# PowerPCB.net
KiCad netlist of a schematic drawn in EAGLE
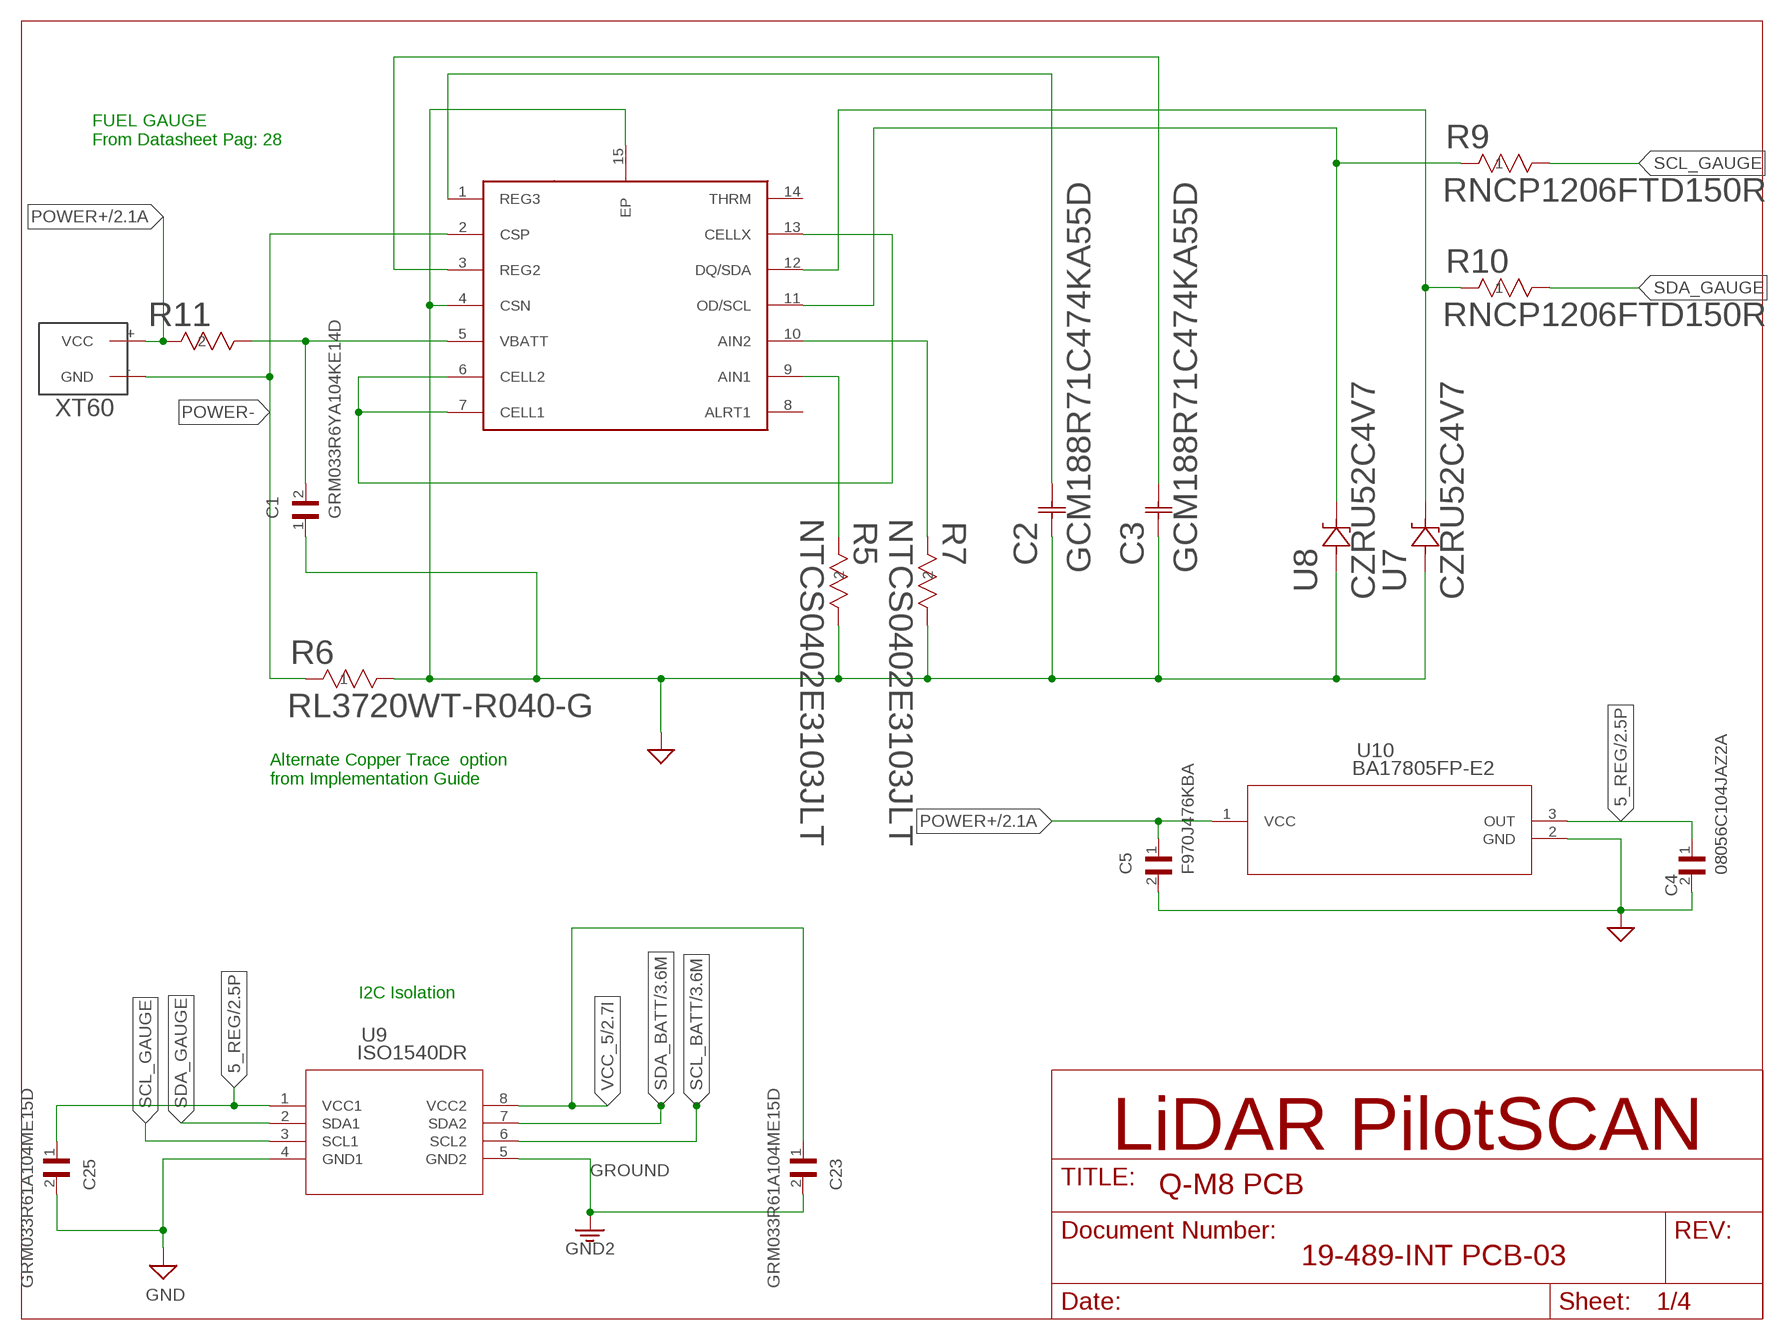
[diagram p0: schematic, sheet 1]
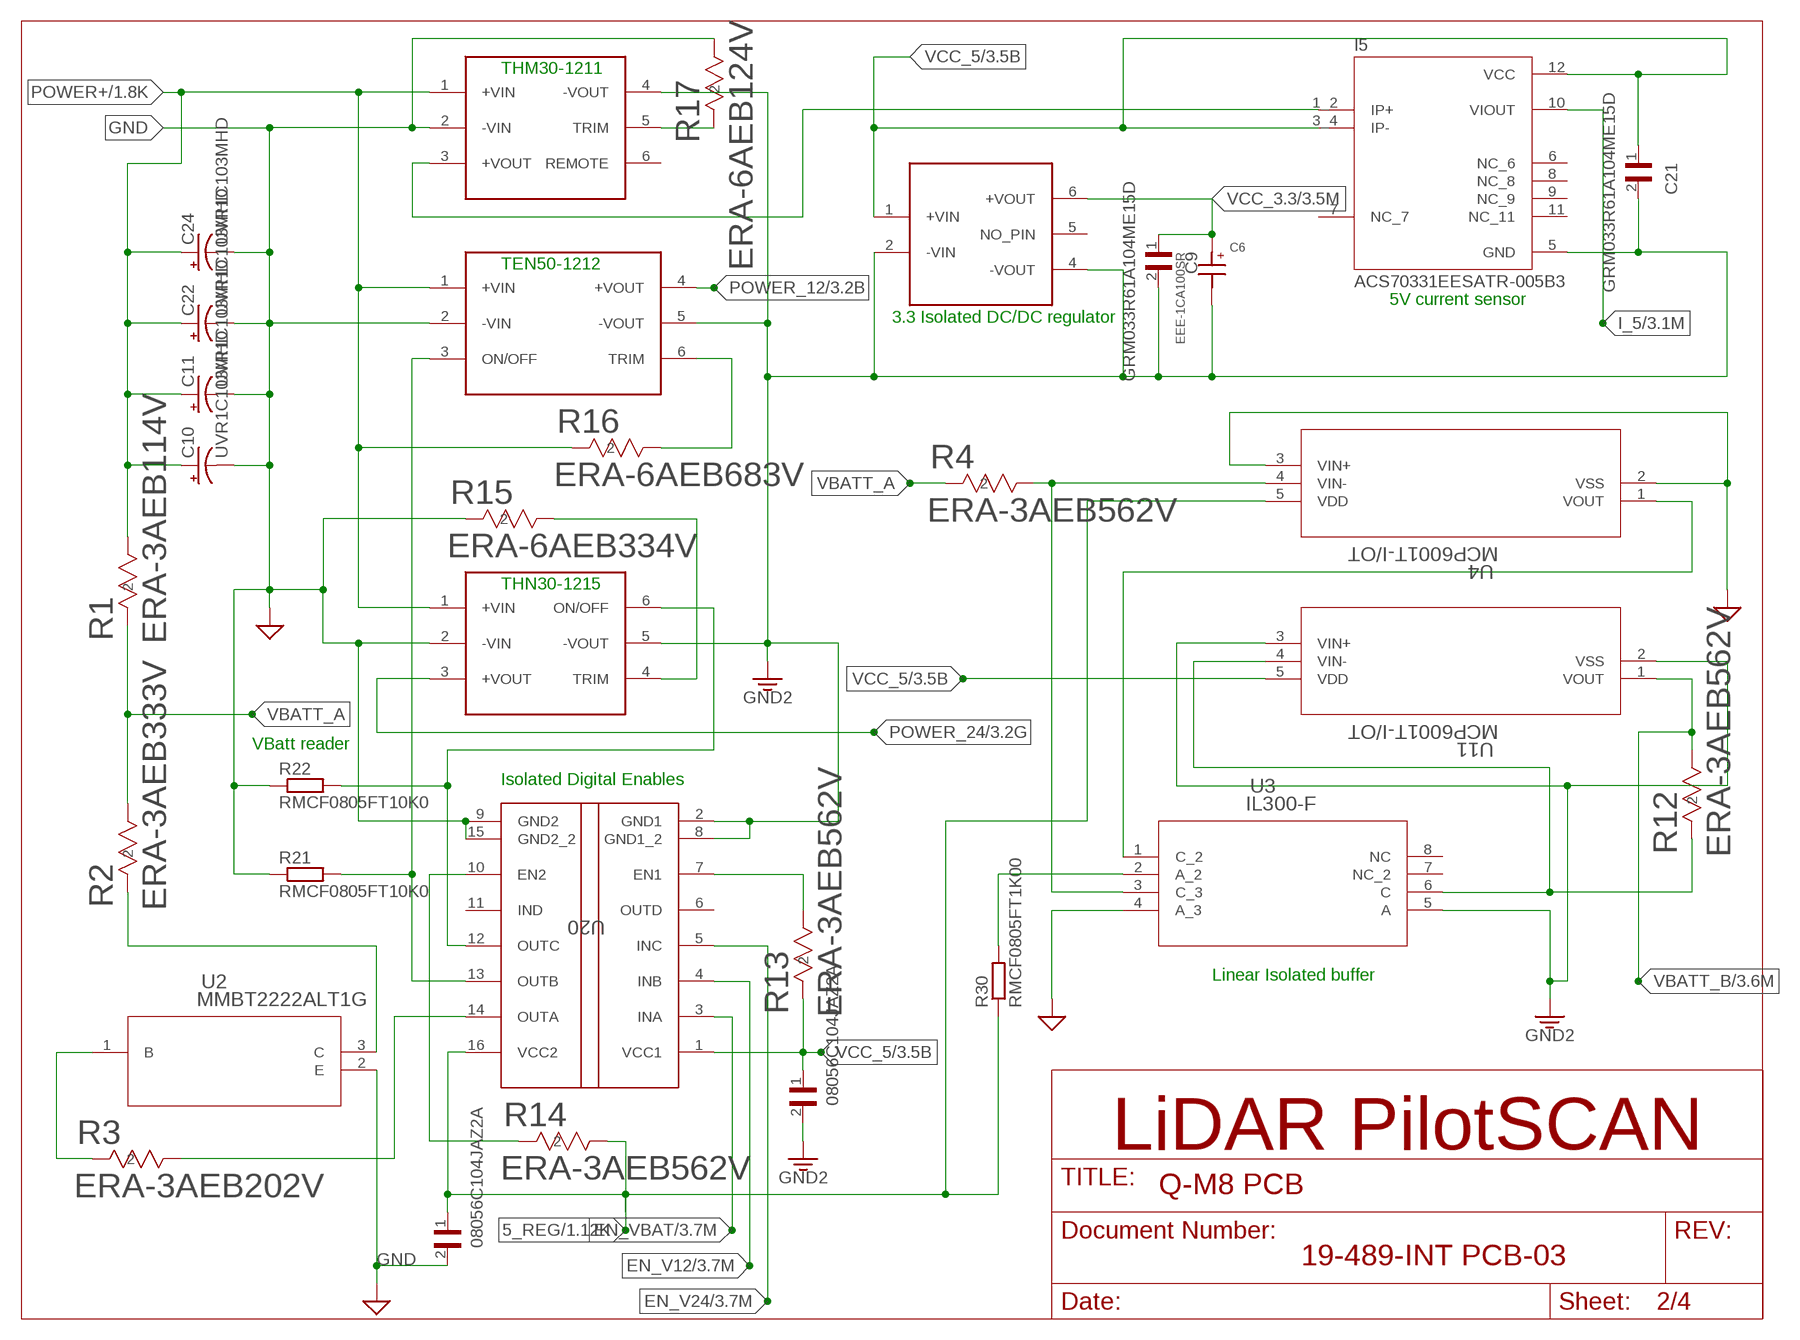
[diagram p1: schematic, sheet 2]
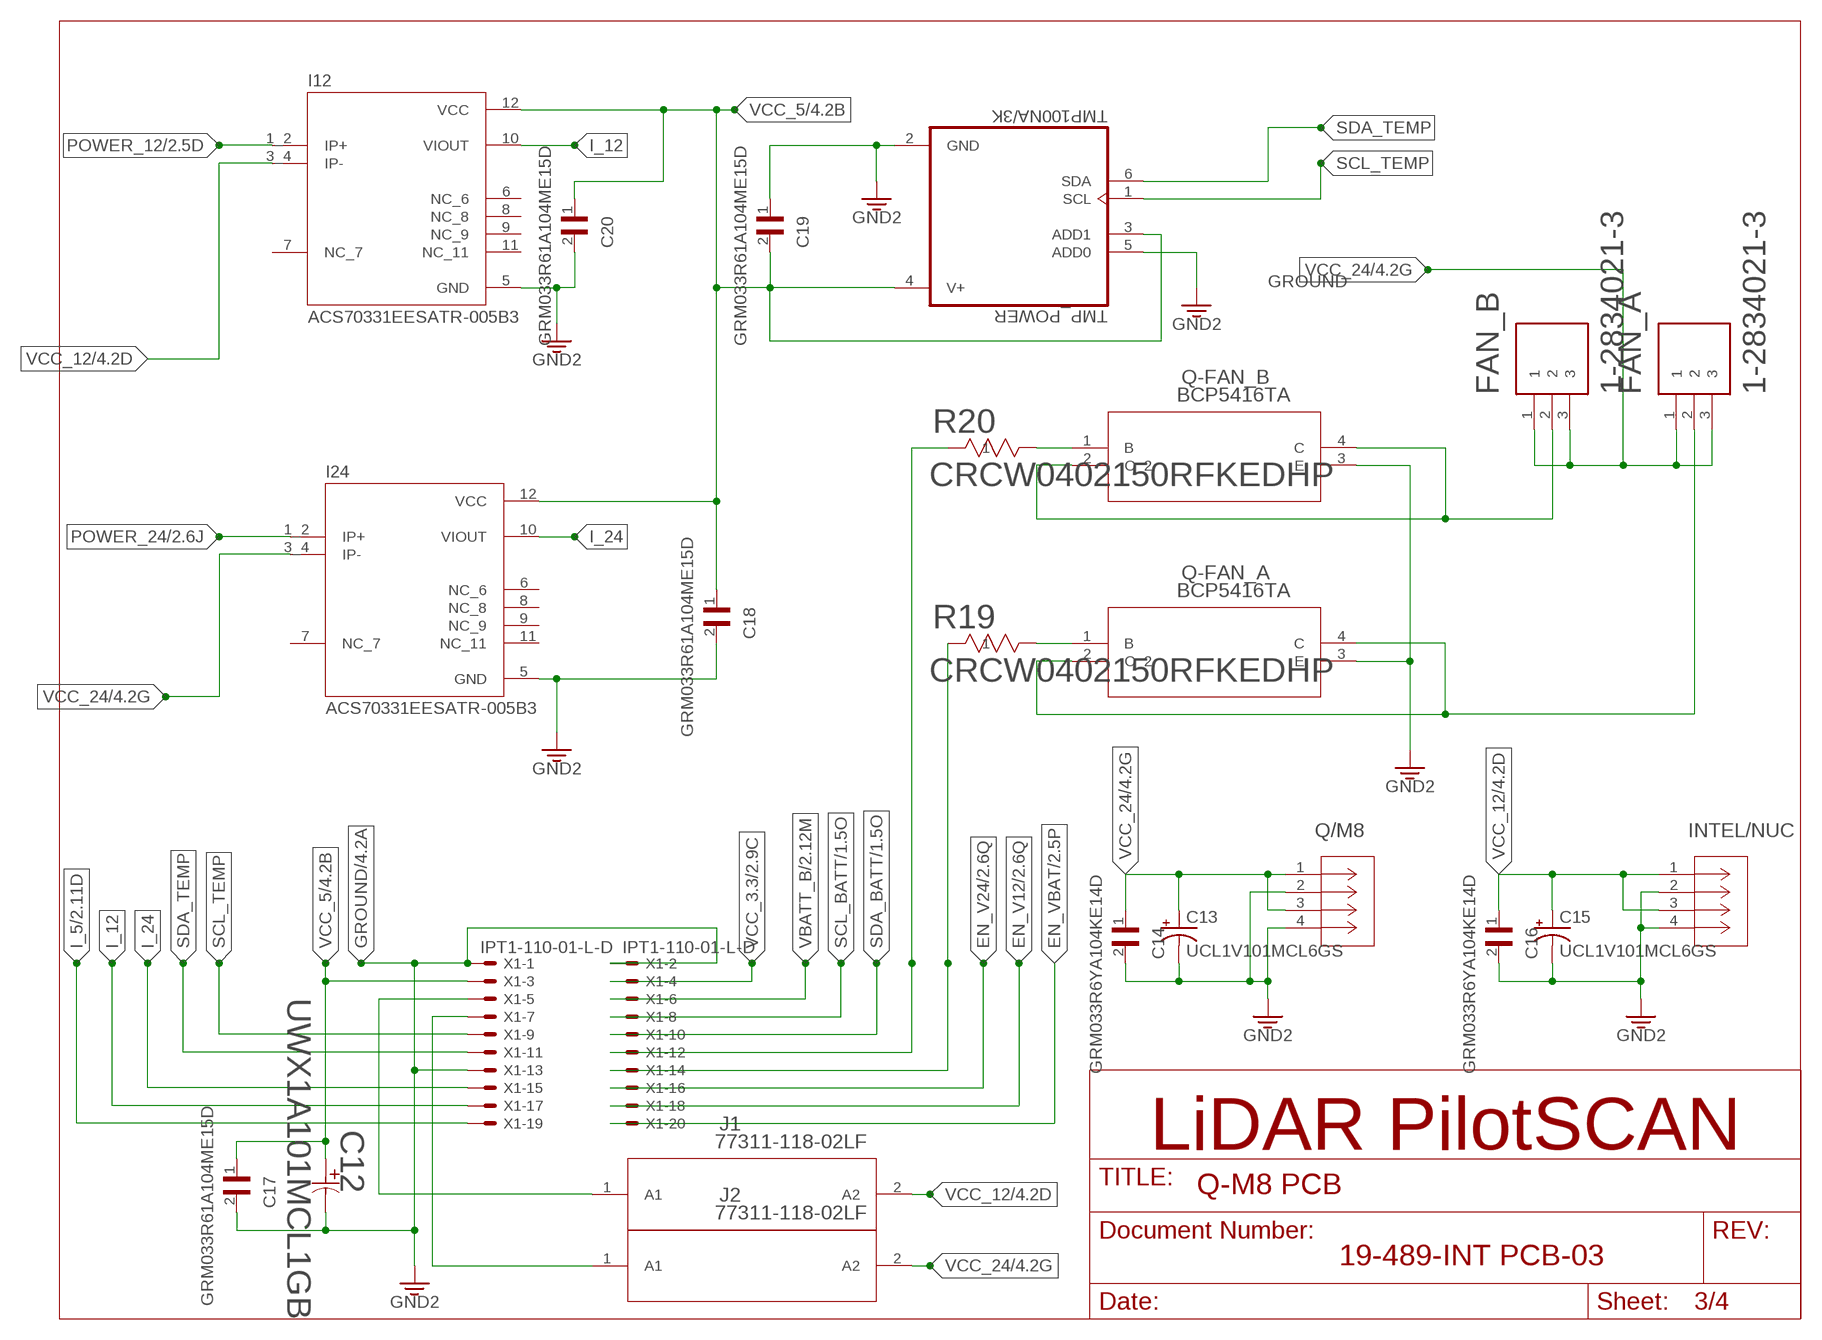
[diagram p2: schematic, sheet 3]
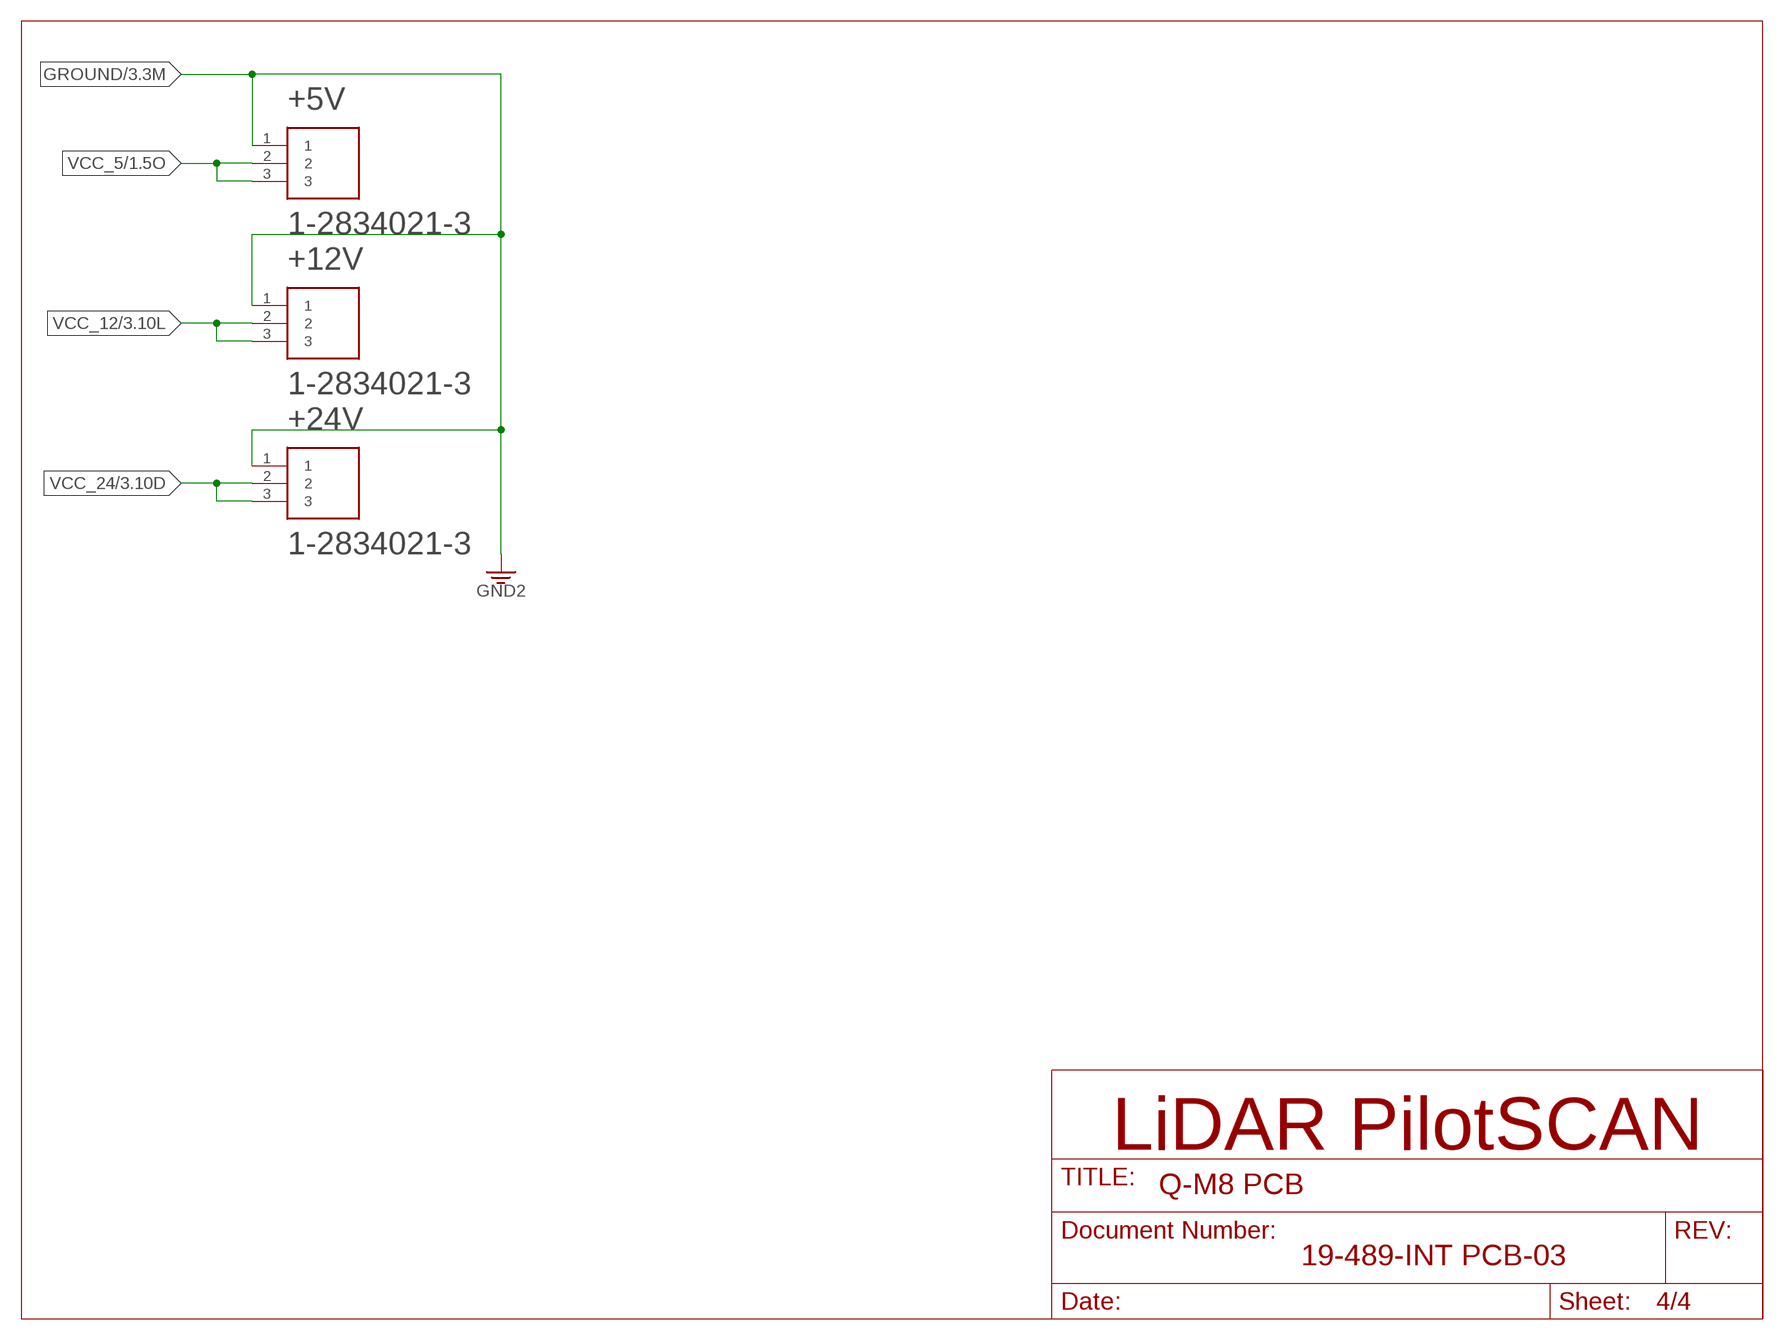
[diagram p3: schematic, sheet 4]

(export (version "E")
  (design (tool "Eeschema 10.0.6"))
  (components
    (comp (ref "+5V")
      (value "1-2834021-3")
      (footprint "eagle-import:CONN_1-2834021-3")
      (fields (field (name "DIGI-KEY_PART_NUMBER") "A123845-ND") (field (name "MF") "TE Connectivity"))
      (libsource (lib "eagle-import") (part "1-2834021-3"))
    )
    (comp (ref "+12V")
      (value "1-2834021-3")
      (footprint "eagle-import:CONN_1-2834021-3")
      (fields (field (name "DIGI-KEY_PART_NUMBER") "A123845-ND") (field (name "MF") "TE Connectivity"))
      (libsource (lib "eagle-import") (part "1-2834021-3"))
    )
    (comp (ref "+24V")
      (value "1-2834021-3")
      (footprint "eagle-import:CONN_1-2834021-3")
      (fields (field (name "DIGI-KEY_PART_NUMBER") "A123845-ND") (field (name "MF") "TE Connectivity"))
      (libsource (lib "eagle-import") (part "1-2834021-3"))
    )
    (comp (ref "C12")
      (value "UWX1A101MCL1GB")
      (footprint "eagle-import:PCAP_6.3X5.4-ELECT")
      (libsource (lib "eagle-import") (part "UWX1A101MCL1GB"))
    )
    (comp (ref "C13")
      (value "UCL1V101MCL6GS")
      (footprint "eagle-import:U2-K")
      (libsource (lib "eagle-import") (part "UCL1V101MCL6GS"))
    )
    (comp (ref "C14")
      (value "GRM033R6YA104KE14D")
      (footprint "eagle-import:CAPC0603X33N")
      (fields (field (name "DIGI-KEY_PART_NUMBER") "490-10430-1-ND") (field (name "MF") "Murata Electronics"))
      (libsource (lib "eagle-import") (part "GRM033R6YA104KE14D"))
    )
    (comp (ref "C15")
      (value "UCL1V101MCL6GS")
      (footprint "eagle-import:U2-K")
      (libsource (lib "eagle-import") (part "UCL1V101MCL6GS"))
    )
    (comp (ref "C16")
      (value "GRM033R6YA104KE14D")
      (footprint "eagle-import:CAPC0603X33N")
      (fields (field (name "DIGI-KEY_PART_NUMBER") "490-10430-1-ND") (field (name "MF") "Murata Electronics"))
      (libsource (lib "eagle-import") (part "GRM033R6YA104KE14D"))
    )
    (comp (ref "C17")
      (value "GRM033R61A104ME15D")
      (footprint "eagle-import:CAPC0603X33N")
      (fields (field (name "DIGI-KEY_PART_NUMBER") "490-5405-1-ND") (field (name "MF") "Murata Electronics"))
      (libsource (lib "eagle-import") (part "GRM033R61A104ME15D"))
    )
    (comp (ref "C18")
      (value "GRM033R61A104ME15D")
      (footprint "eagle-import:CAPC0603X33N")
      (fields (field (name "DIGI-KEY_PART_NUMBER") "490-5405-1-ND") (field (name "MF") "Murata Electronics"))
      (libsource (lib "eagle-import") (part "GRM033R61A104ME15D"))
    )
    (comp (ref "C19")
      (value "GRM033R61A104ME15D")
      (footprint "eagle-import:CAPC0603X33N")
      (fields (field (name "DIGI-KEY_PART_NUMBER") "490-5405-1-ND") (field (name "MF") "Murata Electronics"))
      (libsource (lib "eagle-import") (part "GRM033R61A104ME15D"))
    )
    (comp (ref "C20")
      (value "GRM033R61A104ME15D")
      (footprint "eagle-import:CAPC0603X33N")
      (fields (field (name "DIGI-KEY_PART_NUMBER") "490-5405-1-ND") (field (name "MF") "Murata Electronics"))
      (libsource (lib "eagle-import") (part "GRM033R61A104ME15D"))
    )
    (comp (ref "FAN_A")
      (value "1-2834021-3")
      (footprint "eagle-import:CONN_1-2834021-3")
      (fields (field (name "DIGI-KEY_PART_NUMBER") "A123845-ND") (field (name "MF") "TE Connectivity"))
      (libsource (lib "eagle-import") (part "1-2834021-3"))
    )
    (comp (ref "FAN_B")
      (value "1-2834021-3")
      (footprint "eagle-import:CONN_1-2834021-3")
      (fields (field (name "DIGI-KEY_PART_NUMBER") "A123845-ND") (field (name "MF") "TE Connectivity"))
      (libsource (lib "eagle-import") (part "1-2834021-3"))
    )
    (comp (ref "I12")
      (value "ACS70331EESATR-005B3")
      (footprint "eagle-import:ACS70331EESATR-2P5U3")
      (fields (field (name "MF") "Allegro MicroSystems LLC"))
      (libsource (lib "eagle-import") (part "ACS70331EESATR-005B3"))
    )
    (comp (ref "I24")
      (value "ACS70331EESATR-005B3")
      (footprint "eagle-import:ACS70331EESATR-2P5U3")
      (fields (field (name "MF") "Allegro MicroSystems LLC"))
      (libsource (lib "eagle-import") (part "ACS70331EESATR-005B3"))
    )
    (comp (ref "INTEL/NUC")
      (value "3-794630-4")
      (footprint "eagle-import:CON4_2X2_P3MM_VMNL2")
      (fields (field (name "MANUFACTURER_PART_NUMBER") "37946304"))
      (libsource (lib "eagle-import") (part "3-794630-4"))
    )
    (comp (ref "J1")
      (value "77311-118-02LF")
      (footprint "eagle-import:77311-118-02LF")
      (fields (field (name "MANUFACTURER_PART_NUMBER") "7731111802LF"))
      (libsource (lib "eagle-import") (part "77311-118-02LF"))
    )
    (comp (ref "J2")
      (value "77311-118-02LF")
      (footprint "eagle-import:77311-118-02LF")
      (fields (field (name "MANUFACTURER_PART_NUMBER") "7731111802LF"))
      (libsource (lib "eagle-import") (part "77311-118-02LF"))
    )
    (comp (ref "Q-FAN_A")
      (value "BCP5416TA")
      (footprint "eagle-import:SOT-223")
      (libsource (lib "eagle-import") (part "BCP5416TA"))
    )
    (comp (ref "Q-FAN_B")
      (value "BCP5416TA")
      (footprint "eagle-import:SOT-223")
      (libsource (lib "eagle-import") (part "BCP5416TA"))
    )
    (comp (ref "Q/M8")
      (value "3-794630-4")
      (footprint "eagle-import:CON4_2X2_P3MM_VMNL2")
      (fields (field (name "MANUFACTURER_PART_NUMBER") "37946304"))
      (libsource (lib "eagle-import") (part "3-794630-4"))
    )
    (comp (ref "R19")
      (value "CRCW0402150RFKEDHP")
      (footprint "eagle-import:RES_CRCW_0402")
      (libsource (lib "eagle-import") (part "CRCW0402150RFKEDHP"))
    )
    (comp (ref "R20")
      (value "CRCW0402150RFKEDHP")
      (footprint "eagle-import:RES_CRCW_0402")
      (libsource (lib "eagle-import") (part "CRCW0402150RFKEDHP"))
    )
    (comp (ref "TMP_POWER")
      (value "TMP100NA/3K")
      (footprint "eagle-import:TMP100NA_3K")
      (fields (field (name "MF") "Texas Instruments"))
      (libsource (lib "eagle-import") (part "TMP100NA/3K"))
    )
    (comp (ref "X1")
      (value "IPT1-110-01-L-D")
      (footprint "eagle-import:IPT1-110-01-L-D")
      (libsource (lib "eagle-import") (part "IPT1-110-01-L-D"))
    )
    (comp (ref "C6")
      (value "EEE-1CA100SR")
      (footprint "eagle-import:CAPAE430X550N")
      (fields (field (name "DIGI-KEY_PART_NUMBER") "PCE3878CT-ND") (field (name "MF") "Panasonic"))
      (libsource (lib "eagle-import") (part "EEE-1CA100SR"))
    )
    (comp (ref "C7")
      (value "08056C104JAZ2A")
      (footprint "eagle-import:CAPC2012X140N")
      (fields (field (name "MF") "AVX"))
      (libsource (lib "eagle-import") (part "08056C104JAZ2A"))
    )
    (comp (ref "C8")
      (value "08056C104JAZ2A")
      (footprint "eagle-import:CAPC2012X140N")
      (fields (field (name "MF") "AVX"))
      (libsource (lib "eagle-import") (part "08056C104JAZ2A"))
    )
    (comp (ref "C9")
      (value "GRM033R61A104ME15D")
      (footprint "eagle-import:CAPC0603X33N")
      (fields (field (name "DIGI-KEY_PART_NUMBER") "490-5405-1-ND") (field (name "MF") "Murata Electronics"))
      (libsource (lib "eagle-import") (part "GRM033R61A104ME15D"))
    )
    (comp (ref "C10")
      (value "UVR1C103MHD")
      (footprint "eagle-import:U1-PP")
      (libsource (lib "eagle-import") (part "UVR1C103MHD"))
    )
    (comp (ref "C11")
      (value "UVR1C103MHD")
      (footprint "eagle-import:U1-PP")
      (libsource (lib "eagle-import") (part "UVR1C103MHD"))
    )
    (comp (ref "C21")
      (value "GRM033R61A104ME15D")
      (footprint "eagle-import:CAPC0603X33N")
      (fields (field (name "DIGI-KEY_PART_NUMBER") "490-5405-1-ND") (field (name "MF") "Murata Electronics"))
      (libsource (lib "eagle-import") (part "GRM033R61A104ME15D"))
    )
    (comp (ref "C22")
      (value "UVR1C103MHD")
      (footprint "eagle-import:U1-PP")
      (libsource (lib "eagle-import") (part "UVR1C103MHD"))
    )
    (comp (ref "C24")
      (value "UVR1C103MHD")
      (footprint "eagle-import:U1-PP")
      (libsource (lib "eagle-import") (part "UVR1C103MHD"))
    )
    (comp (ref "DCDC5")
      (value "THM30-1211")
      (footprint "eagle-import:THM30-1211")
      (libsource (lib "eagle-import") (part "THM30-1211"))
    )
    (comp (ref "DCDC12")
      (value "TEN50-1212")
      (footprint "eagle-import:TEN50-1212")
      (libsource (lib "eagle-import") (part "TEN50-1212"))
    )
    (comp (ref "DCDC24")
      (value "THN30-1215")
      (footprint "eagle-import:THN30-1215")
      (libsource (lib "eagle-import") (part "THN30-1215"))
    )
    (comp (ref "I5")
      (value "ACS70331EESATR-005B3")
      (footprint "eagle-import:ACS70331EESATR-2P5U3")
      (fields (field (name "MF") "Allegro MicroSystems LLC"))
      (libsource (lib "eagle-import") (part "ACS70331EESATR-005B3"))
    )
    (comp (ref "R1")
      (value "ERA-3AEB114V")
      (footprint "eagle-import:RC0603N")
      (fields (field (name "MANUFACTURER_PART_NUMBER") "ERA3AEB114V"))
      (libsource (lib "eagle-import") (part "ERA-3AEB114V"))
    )
    (comp (ref "R2")
      (value "ERA-3AEB333V")
      (footprint "eagle-import:RC0603N")
      (fields (field (name "MANUFACTURER_PART_NUMBER") "ERA3AEB333V"))
      (libsource (lib "eagle-import") (part "ERA-3AEB333V"))
    )
    (comp (ref "R3")
      (value "ERA-3AEB202V")
      (footprint "eagle-import:RC0603N")
      (fields (field (name "MANUFACTURER_PART_NUMBER") "ERA3AEB202V"))
      (libsource (lib "eagle-import") (part "ERA-3AEB202V"))
    )
    (comp (ref "R4")
      (value "ERA-3AEB562V")
      (footprint "eagle-import:RC0603N")
      (fields (field (name "MANUFACTURER_PART_NUMBER") "ERA3AEB562V"))
      (libsource (lib "eagle-import") (part "ERA-3AEB562V"))
    )
    (comp (ref "R12")
      (value "ERA-3AEB562V")
      (footprint "eagle-import:RC0603N")
      (fields (field (name "MANUFACTURER_PART_NUMBER") "ERA3AEB562V"))
      (libsource (lib "eagle-import") (part "ERA-3AEB562V"))
    )
    (comp (ref "R13")
      (value "ERA-3AEB562V")
      (footprint "eagle-import:RC0603N")
      (fields (field (name "MANUFACTURER_PART_NUMBER") "ERA3AEB562V"))
      (libsource (lib "eagle-import") (part "ERA-3AEB562V"))
    )
    (comp (ref "R14")
      (value "ERA-3AEB562V")
      (footprint "eagle-import:RC0603N")
      (fields (field (name "MANUFACTURER_PART_NUMBER") "ERA3AEB562V"))
      (libsource (lib "eagle-import") (part "ERA-3AEB562V"))
    )
    (comp (ref "R15")
      (value "ERA-6AEB334V")
      (footprint "eagle-import:RC0805N")
      (fields (field (name "MANUFACTURER_PART_NUMBER") "ERA6AEB334V"))
      (libsource (lib "eagle-import") (part "ERA-6AEB334V"))
    )
    (comp (ref "R16")
      (value "ERA-6AEB683V")
      (footprint "eagle-import:RC0805N")
      (fields (field (name "MANUFACTURER_PART_NUMBER") "ERA6AEB683V"))
      (libsource (lib "eagle-import") (part "ERA-6AEB683V"))
    )
    (comp (ref "R17")
      (value "ERA-6AEB124V")
      (footprint "eagle-import:RC0805N")
      (fields (field (name "MANUFACTURER_PART_NUMBER") "ERA6AEB124V"))
      (libsource (lib "eagle-import") (part "ERA-6AEB124V"))
    )
    (comp (ref "R21")
      (value "RMCF0805FT10K0")
      (footprint "eagle-import:RMCF0805FT10K0")
      (libsource (lib "eagle-import") (part "RMCF0805FT10K0"))
    )
    (comp (ref "R22")
      (value "RMCF0805FT10K0")
      (footprint "eagle-import:RMCF0805FT10K0")
      (libsource (lib "eagle-import") (part "RMCF0805FT10K0"))
    )
    (comp (ref "R30")
      (value "RMCF0805FT1K00")
      (footprint "eagle-import:RMCF0805FT1K00")
      (libsource (lib "eagle-import") (part "RMCF0805FT1K00"))
    )
    (comp (ref "U2")
      (value "MMBT2222ALT1G")
      (footprint "eagle-import:SOT-23")
      (libsource (lib "eagle-import") (part "MMBT2222ALT1G"))
    )
    (comp (ref "U3")
      (value "IL300-F")
      (footprint "eagle-import:DIP8_IL")
      (fields (field (name "MANUFACTURER_PART_NUMBER") "IL300F"))
      (libsource (lib "eagle-import") (part "IL300-F"))
    )
    (comp (ref "U4")
      (value "MCP6001T-I/OT")
      (footprint "eagle-import:SOT-23-5_MC")
      (fields (field (name "MANUFACTURER_PART_NUMBER") "MCP6001TIOT"))
      (libsource (lib "eagle-import") (part "MCP6001T-I/OT"))
    )
    (comp (ref "U6")
      (value "TMV0503SHI")
      (footprint "eagle-import:TMV0503SHI")
      (libsource (lib "eagle-import") (part "TMV0503SHI"))
    )
    (comp (ref "U11")
      (value "MCP6001T-I/OT")
      (footprint "eagle-import:SOT-23-5_MC")
      (fields (field (name "MANUFACTURER_PART_NUMBER") "MCP6001TIOT"))
      (libsource (lib "eagle-import") (part "MCP6001T-I/OT"))
    )
    (comp (ref "U20")
      (value "ISO7741DBQR")
      (footprint "eagle-import:DBQ0016A_N")
      (libsource (lib "eagle-import") (part "ISO7741DBQR"))
    )
    (comp (ref "C1")
      (value "GRM033R6YA104KE14D")
      (footprint "eagle-import:CAPC0603X33N")
      (fields (field (name "DIGI-KEY_PART_NUMBER") "490-10430-1-ND") (field (name "MF") "Murata Electronics"))
      (libsource (lib "eagle-import") (part "GRM033R6YA104KE14D"))
    )
    (comp (ref "C2")
      (value "GCM188R71C474KA55D")
      (footprint "eagle-import:G-188")
      (libsource (lib "eagle-import") (part "GCM188R71C474KA55D"))
    )
    (comp (ref "C3")
      (value "GCM188R71C474KA55D")
      (footprint "eagle-import:G-188")
      (libsource (lib "eagle-import") (part "GCM188R71C474KA55D"))
    )
    (comp (ref "C4")
      (value "08056C104JAZ2A")
      (footprint "eagle-import:CAPC2012X140N")
      (fields (field (name "MF") "AVX"))
      (libsource (lib "eagle-import") (part "08056C104JAZ2A"))
    )
    (comp (ref "C5")
      (value "F970J476KBA")
      (footprint "eagle-import:CAPPC3528X210N")
      (fields (field (name "MF") "AVX"))
      (libsource (lib "eagle-import") (part "F970J476KBA"))
    )
    (comp (ref "C23")
      (value "GRM033R61A104ME15D")
      (footprint "eagle-import:CAPC0603X33N")
      (fields (field (name "DIGI-KEY_PART_NUMBER") "490-5405-1-ND") (field (name "MF") "Murata Electronics"))
      (libsource (lib "eagle-import") (part "GRM033R61A104ME15D"))
    )
    (comp (ref "C25")
      (value "GRM033R61A104ME15D")
      (footprint "eagle-import:CAPC0603X33N")
      (fields (field (name "DIGI-KEY_PART_NUMBER") "490-5405-1-ND") (field (name "MF") "Murata Electronics"))
      (libsource (lib "eagle-import") (part "GRM033R61A104ME15D"))
    )
    (comp (ref "J5")
      (value "XT60")
      (footprint "eagle-import:XT60")
      (libsource (lib "eagle-import") (part "XT60"))
    )
    (comp (ref "R5")
      (value "NTCS0402E3103JLT")
      (footprint "eagle-import:RES_0402_NTC")
      (libsource (lib "eagle-import") (part "NTCS0402E3103JLT"))
    )
    (comp (ref "R6")
      (value "RL3720WT-R040-G")
      (footprint "eagle-import:RES_2037")
      (fields (field (name "MANUFACTURER_PART_NUMBER") "RL3720WTR040G"))
      (libsource (lib "eagle-import") (part "RL3720WT-R040-G"))
    )
    (comp (ref "R7")
      (value "NTCS0402E3103JLT")
      (footprint "eagle-import:RES_0402_NTC")
      (libsource (lib "eagle-import") (part "NTCS0402E3103JLT"))
    )
    (comp (ref "R9")
      (value "RNCP1206FTD150R")
      (footprint "eagle-import:STA_RNCP1206")
      (libsource (lib "eagle-import") (part "RNCP1206FTD150R"))
    )
    (comp (ref "R10")
      (value "RNCP1206FTD150R")
      (footprint "eagle-import:STA_RNCP1206")
      (libsource (lib "eagle-import") (part "RNCP1206FTD150R"))
    )
    (comp (ref "R11")
      (value "ERA-2AKD100X")
      (footprint "eagle-import:RC0402N")
      (fields (field (name "MANUFACTURER_PART_NUMBER") "ERA2AKD100X"))
      (libsource (lib "eagle-import") (part "ERA-2AKD100X"))
    )
    (comp (ref "U5")
      (value "MAX17205G+T")
      (footprint "eagle-import:MAX17205G+T")
      (fields (field (name "MANUFACTURER") "Maxim Integrated"))
      (libsource (lib "eagle-import") (part "MAX17205G+T"))
    )
    (comp (ref "U7")
      (value "CZRU52C4V7")
      (footprint "eagle-import:CZRU")
      (libsource (lib "eagle-import") (part "CZRU52C4V7"))
    )
    (comp (ref "U8")
      (value "CZRU52C4V7")
      (footprint "eagle-import:CZRU")
      (libsource (lib "eagle-import") (part "CZRU52C4V7"))
    )
    (comp (ref "U9")
      (value "ISO1540DR")
      (footprint "eagle-import:D8")
      (libsource (lib "eagle-import") (part "ISO1540DR"))
    )
    (comp (ref "U10")
      (value "BA17805FP-E2")
      (footprint "eagle-import:TO252-3")
      (fields (field (name "MANUFACTURER_PART_NUMBER") "BA17805FPE2"))
      (libsource (lib "eagle-import") (part "BA17805FP-E2"))
    )
  )
  (nets
    (net (code "1") (name "5_REG") (class "Default")
      (node (ref "C25") (pin "1") (pinfunction "1_1") (pintype "passive"))
      (node (ref "C4") (pin "1") (pinfunction "1_1") (pintype "passive"))
      (node (ref "C8") (pin "1") (pinfunction "1_1") (pintype "passive"))
      (node (ref "R14") (pin "1") (pinfunction "1_1") (pintype "passive"))
      (node (ref "R30") (pin "1") (pinfunction "1_1") (pintype "passive"))
      (node (ref "U10") (pin "3") (pinfunction "OUT_3") (pintype "output"))
      (node (ref "U20") (pin "16") (pinfunction "VCC2_16") (pintype "power_in"))
      (node (ref "U4") (pin "5") (pinfunction "VDD_5") (pintype "passive"))
      (node (ref "U9") (pin "1") (pinfunction "VCC1_1") (pintype "power_in"))
    )
    (net (code "2") (name "EN_V12") (class "Default")
      (node (ref "U20") (pin "4") (pinfunction "INB_4") (pintype "input"))
      (node (ref "X1") (pin "P$18") (pinfunction "S_P$18") (pintype "passive"))
    )
    (net (code "3") (name "EN_V24") (class "Default")
      (node (ref "U20") (pin "5") (pinfunction "INC_5") (pintype "input"))
      (node (ref "X1") (pin "P$16") (pinfunction "S_P$16") (pintype "passive"))
    )
    (net (code "4") (name "EN_VBAT") (class "Default")
      (node (ref "U20") (pin "3") (pinfunction "INA_3") (pintype "input"))
      (node (ref "X1") (pin "P$20") (pinfunction "S_P$20") (pintype "passive"))
    )
    (net (code "5") (name "GND") (class "Default")
      (node (ref "C1") (pin "1") (pinfunction "1_1") (pintype "passive"))
      (node (ref "C10") (pin "2") (pinfunction "-_2") (pintype "passive"))
      (node (ref "C11") (pin "2") (pinfunction "-_2") (pintype "passive"))
      (node (ref "C2") (pin "1") (pinfunction "1_1") (pintype "passive"))
      (node (ref "C22") (pin "2") (pinfunction "-_2") (pintype "passive"))
      (node (ref "C24") (pin "2") (pinfunction "-_2") (pintype "passive"))
      (node (ref "C25") (pin "2") (pinfunction "2_2") (pintype "passive"))
      (node (ref "C3") (pin "1") (pinfunction "1_1") (pintype "passive"))
      (node (ref "C4") (pin "2") (pinfunction "2_2") (pintype "passive"))
      (node (ref "C5") (pin "2") (pinfunction "2_2") (pintype "passive"))
      (node (ref "C8") (pin "2") (pinfunction "2_2") (pintype "passive"))
      (node (ref "DCDC12") (pin "2") (pinfunction "-VIN_2") (pintype "bidirectional"))
      (node (ref "DCDC24") (pin "2") (pinfunction "-VIN_2") (pintype "bidirectional"))
      (node (ref "DCDC5") (pin "2") (pinfunction "-VIN_2") (pintype "bidirectional"))
      (node (ref "R15") (pin "2") (pinfunction "2_2") (pintype "passive"))
      (node (ref "R17") (pin "1") (pinfunction "1_1") (pintype "passive"))
      (node (ref "R21") (pin "1") (pinfunction "1_1") (pintype "passive"))
      (node (ref "R22") (pin "1") (pinfunction "1_1") (pintype "passive"))
      (node (ref "R5") (pin "1") (pinfunction "1_1") (pintype "passive"))
      (node (ref "R6") (pin "2") (pinfunction "2_2") (pintype "passive"))
      (node (ref "R7") (pin "1") (pinfunction "1_1") (pintype "passive"))
      (node (ref "U10") (pin "2") (pinfunction "GND_2") (pintype "power_in"))
      (node (ref "U2") (pin "2") (pinfunction "E_2") (pintype "passive"))
      (node (ref "U20") (pin "15") (pinfunction "GND2_2_15") (pintype "power_in"))
      (node (ref "U20") (pin "9") (pinfunction "GND2_9") (pintype "power_in"))
      (node (ref "U3") (pin "4") (pinfunction "A_3_4") (pintype "passive"))
      (node (ref "U4") (pin "2") (pinfunction "VSS_2") (pintype "passive"))
      (node (ref "U4") (pin "3") (pinfunction "VIN+_3") (pintype "passive"))
      (node (ref "U5") (pin "15") (pinfunction "EP_15") (pintype "bidirectional"))
      (node (ref "U5") (pin "4") (pinfunction "CSN_4") (pintype "bidirectional"))
      (node (ref "U7") (pin "2") (pinfunction "2_2") (pintype "passive"))
      (node (ref "U8") (pin "2") (pinfunction "2_2") (pintype "passive"))
      (node (ref "U9") (pin "4") (pinfunction "GND1_4") (pintype "power_in"))
    )
    (net (code "6") (name "GROUND") (class "Default")
      (node (ref "+12V") (pin "1") (pinfunction "1_1") (pintype "passive"))
      (node (ref "+24V") (pin "1") (pinfunction "1_1") (pintype "passive"))
      (node (ref "+5V") (pin "1") (pinfunction "1_1") (pintype "passive"))
      (node (ref "C12") (pin "2") (pinfunction "2_2") (pintype "passive"))
      (node (ref "C13") (pin "2") (pinfunction "-_2") (pintype "passive"))
      (node (ref "C14") (pin "2") (pinfunction "2_2") (pintype "passive"))
      (node (ref "C15") (pin "2") (pinfunction "-_2") (pintype "passive"))
      (node (ref "C16") (pin "2") (pinfunction "2_2") (pintype "passive"))
      (node (ref "C17") (pin "2") (pinfunction "2_2") (pintype "passive"))
      (node (ref "C18") (pin "2") (pinfunction "2_2") (pintype "passive"))
      (node (ref "C19") (pin "1") (pinfunction "1_1") (pintype "passive"))
      (node (ref "C20") (pin "2") (pinfunction "2_2") (pintype "passive"))
      (node (ref "C21") (pin "2") (pinfunction "2_2") (pintype "passive"))
      (node (ref "C23") (pin "2") (pinfunction "2_2") (pintype "passive"))
      (node (ref "C6") (pin "2") (pinfunction "2_2") (pintype "passive"))
      (node (ref "C7") (pin "2") (pinfunction "2_2") (pintype "passive"))
      (node (ref "C9") (pin "2") (pinfunction "2_2") (pintype "passive"))
      (node (ref "DCDC12") (pin "5") (pinfunction "-VOUT_5") (pintype "bidirectional"))
      (node (ref "DCDC24") (pin "5") (pinfunction "-VOUT_5") (pintype "bidirectional"))
      (node (ref "DCDC5") (pin "4") (pinfunction "-VOUT_4") (pintype "bidirectional"))
      (node (ref "I12") (pin "5") (pinfunction "GND_5") (pintype "power_in"))
      (node (ref "I24") (pin "5") (pinfunction "GND_5") (pintype "power_in"))
      (node (ref "I5") (pin "5") (pinfunction "GND_5") (pintype "power_in"))
      (node (ref "INTEL/NUC") (pin "2") (pinfunction "2_2") (pintype "passive"))
      (node (ref "INTEL/NUC") (pin "4") (pinfunction "4_4") (pintype "passive"))
      (node (ref "Q-FAN_A") (pin "3") (pinfunction "E_3") (pintype "passive"))
      (node (ref "Q-FAN_B") (pin "3") (pinfunction "E_3") (pintype "passive"))
      (node (ref "Q/M8") (pin "2") (pinfunction "2_2") (pintype "passive"))
      (node (ref "Q/M8") (pin "4") (pinfunction "4_4") (pintype "passive"))
      (node (ref "TMP_POWER") (pin "2") (pinfunction "GND_2") (pintype "power_in"))
      (node (ref "TMP_POWER") (pin "5") (pinfunction "ADD0_5") (pintype "input"))
      (node (ref "U11") (pin "2") (pinfunction "VSS_2") (pintype "passive"))
      (node (ref "U11") (pin "3") (pinfunction "VIN+_3") (pintype "passive"))
      (node (ref "U20") (pin "2") (pinfunction "GND1_2") (pintype "power_in"))
      (node (ref "U20") (pin "8") (pinfunction "GND1_2_8") (pintype "power_in"))
      (node (ref "U3") (pin "5") (pinfunction "A_5") (pintype "passive"))
      (node (ref "U6") (pin "2") (pinfunction "-VIN_2") (pintype "bidirectional"))
      (node (ref "U6") (pin "4") (pinfunction "-VOUT_4") (pintype "bidirectional"))
      (node (ref "U9") (pin "5") (pinfunction "GND2_5") (pintype "power_in"))
      (node (ref "X1") (pin "P$1") (pinfunction "S_P$1") (pintype "passive"))
      (node (ref "X1") (pin "P$13") (pinfunction "S_P$13") (pintype "passive"))
      (node (ref "X1") (pin "P$2") (pinfunction "S_P$2") (pintype "passive"))
    )
    (net (code "7") (name "I_5") (class "Default")
      (node (ref "I5") (pin "10") (pinfunction "VIOUT_10") (pintype "output"))
      (node (ref "X1") (pin "P$19") (pinfunction "S_P$19") (pintype "passive"))
    )
    (net (code "8") (name "I_12") (class "Default")
      (node (ref "I12") (pin "10") (pinfunction "VIOUT_10") (pintype "output"))
      (node (ref "X1") (pin "P$17") (pinfunction "S_P$17") (pintype "passive"))
    )
    (net (code "9") (name "I_24") (class "Default")
      (node (ref "I24") (pin "10") (pinfunction "VIOUT_10") (pintype "output"))
      (node (ref "X1") (pin "P$15") (pinfunction "S_P$15") (pintype "passive"))
    )
    (net (code "10") (name "Net-(DCDC5-+VOUT)") (class "Default")
      (node (ref "DCDC5") (pin "3") (pinfunction "+VOUT_3") (pintype "bidirectional"))
      (node (ref "I5") (pin "1_2") (pinfunction "IP+_1_2") (pintype "input"))
    )
    (net (code "11") (name "Net-(DCDC5-TRIM)") (class "Default")
      (node (ref "DCDC5") (pin "5") (pinfunction "TRIM_5") (pintype "bidirectional"))
      (node (ref "R17") (pin "2") (pinfunction "2_2") (pintype "passive"))
    )
    (net (code "12") (name "Net-(DCDC12-ON{slash}OFF)") (class "Default")
      (node (ref "DCDC12") (pin "3") (pinfunction "ON/OFF_3") (pintype "bidirectional"))
      (node (ref "R21") (pin "2") (pinfunction "2_2") (pintype "passive"))
      (node (ref "U20") (pin "13") (pinfunction "OUTB_13") (pintype "tri_state"))
    )
    (net (code "13") (name "Net-(DCDC12-TRIM)") (class "Default")
      (node (ref "DCDC12") (pin "6") (pinfunction "TRIM_6") (pintype "bidirectional"))
      (node (ref "R16") (pin "1") (pinfunction "1_1") (pintype "passive"))
    )
    (net (code "14") (name "Net-(DCDC24-ON{slash}OFF)") (class "Default")
      (node (ref "DCDC24") (pin "6") (pinfunction "ON/OFF_6") (pintype "bidirectional"))
      (node (ref "R22") (pin "2") (pinfunction "2_2") (pintype "passive"))
      (node (ref "U20") (pin "12") (pinfunction "OUTC_12") (pintype "tri_state"))
    )
    (net (code "15") (name "Net-(DCDC24-TRIM)") (class "Default")
      (node (ref "DCDC24") (pin "4") (pinfunction "TRIM_4") (pintype "bidirectional"))
      (node (ref "R15") (pin "1") (pinfunction "1_1") (pintype "passive"))
    )
    (net (code "16") (name "Net-(J1-A1)") (class "Default")
      (node (ref "J1") (pin "1") (pinfunction "A1_1") (pintype "passive"))
      (node (ref "X1") (pin "P$5") (pinfunction "S_P$5") (pintype "passive"))
    )
    (net (code "17") (name "Net-(J2-A1)") (class "Default")
      (node (ref "J2") (pin "1") (pinfunction "A1_1") (pintype "passive"))
      (node (ref "X1") (pin "P$7") (pinfunction "S_P$7") (pintype "passive"))
    )
    (net (code "18") (name "Net-(Q-FAN_A-B)") (class "Default")
      (node (ref "Q-FAN_A") (pin "1") (pinfunction "B_1") (pintype "passive"))
      (node (ref "R19") (pin "2") (pinfunction "2_2") (pintype "passive"))
    )
    (net (code "19") (name "Net-(Q-FAN_A-C)") (class "Default")
      (node (ref "FAN_A") (pin "2") (pinfunction "2_2") (pintype "passive"))
      (node (ref "Q-FAN_A") (pin "2") (pinfunction "C_2_2") (pintype "passive"))
      (node (ref "Q-FAN_A") (pin "4") (pinfunction "C_4") (pintype "passive"))
    )
    (net (code "20") (name "Net-(Q-FAN_B-B)") (class "Default")
      (node (ref "Q-FAN_B") (pin "1") (pinfunction "B_1") (pintype "passive"))
      (node (ref "R20") (pin "2") (pinfunction "2_2") (pintype "passive"))
    )
    (net (code "21") (name "Net-(Q-FAN_B-C)") (class "Default")
      (node (ref "FAN_B") (pin "2") (pinfunction "2_2") (pintype "passive"))
      (node (ref "Q-FAN_B") (pin "2") (pinfunction "C_2_2") (pintype "passive"))
      (node (ref "Q-FAN_B") (pin "4") (pinfunction "C_4") (pintype "passive"))
    )
    (net (code "22") (name "Net-(U2-B)") (class "Default")
      (node (ref "R3") (pin "2") (pinfunction "2_2") (pintype "passive"))
      (node (ref "U2") (pin "1") (pinfunction "B_1") (pintype "passive"))
    )
    (net (code "23") (name "Net-(U2-C)") (class "Default")
      (node (ref "R2") (pin "2") (pinfunction "2_2") (pintype "passive"))
      (node (ref "U2") (pin "3") (pinfunction "C_3") (pintype "passive"))
    )
    (net (code "24") (name "Net-(U3-A_2)") (class "Default")
      (node (ref "R30") (pin "2") (pinfunction "2_2") (pintype "passive"))
      (node (ref "U3") (pin "2") (pinfunction "A_2_2") (pintype "passive"))
    )
    (net (code "25") (name "Net-(U3-C_2)") (class "Default")
      (node (ref "U3") (pin "1") (pinfunction "C_2_1") (pintype "passive"))
      (node (ref "U4") (pin "1") (pinfunction "VOUT_1") (pintype "passive"))
    )
    (net (code "26") (name "Net-(U3-C_3)") (class "Default")
      (node (ref "R4") (pin "1") (pinfunction "1_1") (pintype "passive"))
      (node (ref "U3") (pin "3") (pinfunction "C_3_3") (pintype "passive"))
      (node (ref "U4") (pin "4") (pinfunction "VIN-_4") (pintype "passive"))
    )
    (net (code "27") (name "Net-(U5-AIN1)") (class "Default")
      (node (ref "R5") (pin "2") (pinfunction "2_2") (pintype "passive"))
      (node (ref "U5") (pin "9") (pinfunction "AIN1_9") (pintype "bidirectional"))
    )
    (net (code "28") (name "Net-(U5-AIN2)") (class "Default")
      (node (ref "R7") (pin "2") (pinfunction "2_2") (pintype "passive"))
      (node (ref "U5") (pin "10") (pinfunction "AIN2_10") (pintype "bidirectional"))
    )
    (net (code "29") (name "Net-(U5-CELL1)") (class "Default")
      (node (ref "U5") (pin "13") (pinfunction "CELLX_13") (pintype "bidirectional"))
      (node (ref "U5") (pin "6") (pinfunction "CELL2_6") (pintype "bidirectional"))
      (node (ref "U5") (pin "7") (pinfunction "CELL1_7") (pintype "bidirectional"))
    )
    (net (code "30") (name "Net-(U5-DQ{slash}SDA)") (class "Default")
      (node (ref "R10") (pin "1") (pinfunction "1_1") (pintype "passive"))
      (node (ref "U5") (pin "12") (pinfunction "DQ/SDA_12") (pintype "bidirectional"))
      (node (ref "U7") (pin "1") (pinfunction "1_1") (pintype "passive"))
    )
    (net (code "31") (name "Net-(U5-OD{slash}SCL)") (class "Default")
      (node (ref "R9") (pin "1") (pinfunction "1_1") (pintype "passive"))
      (node (ref "U5") (pin "11") (pinfunction "OD/SCL_11") (pintype "bidirectional"))
      (node (ref "U8") (pin "1") (pinfunction "1_1") (pintype "passive"))
    )
    (net (code "32") (name "Net-(U5-REG2)") (class "Default")
      (node (ref "C3") (pin "2") (pinfunction "2_2") (pintype "passive"))
      (node (ref "U5") (pin "3") (pinfunction "REG2_3") (pintype "bidirectional"))
    )
    (net (code "33") (name "Net-(U5-REG3)") (class "Default")
      (node (ref "C2") (pin "2") (pinfunction "2_2") (pintype "passive"))
      (node (ref "U5") (pin "1") (pinfunction "REG3_1") (pintype "bidirectional"))
    )
    (net (code "34") (name "Net-(U5-VBATT)") (class "Default")
      (node (ref "C1") (pin "2") (pinfunction "2_2") (pintype "passive"))
      (node (ref "R11") (pin "1") (pinfunction "1_1") (pintype "passive"))
      (node (ref "U5") (pin "5") (pinfunction "VBATT_5") (pintype "bidirectional"))
    )
    (net (code "35") (name "Net-(U11-VIN-)") (class "Default")
      (node (ref "R12") (pin "2") (pinfunction "2_2") (pintype "passive"))
      (node (ref "U11") (pin "4") (pinfunction "VIN-_4") (pintype "passive"))
      (node (ref "U3") (pin "6") (pinfunction "C_6") (pintype "passive"))
    )
    (net (code "36") (name "Net-(U20-EN1)") (class "Default")
      (node (ref "R13") (pin "1") (pinfunction "1_1") (pintype "passive"))
      (node (ref "U20") (pin "7") (pinfunction "EN1_7") (pintype "input"))
    )
    (net (code "37") (name "Net-(U20-EN2)") (class "Default")
      (node (ref "R14") (pin "2") (pinfunction "2_2") (pintype "passive"))
      (node (ref "U20") (pin "10") (pinfunction "EN2_10") (pintype "input"))
    )
    (net (code "38") (name "Net-(U20-OUTA)") (class "Default")
      (node (ref "R3") (pin "1") (pinfunction "1_1") (pintype "passive"))
      (node (ref "U20") (pin "14") (pinfunction "OUTA_14") (pintype "tri_state"))
    )
    (net (code "39") (name "Net-(X1D-S)") (class "Default")
      (node (ref "R20") (pin "1") (pinfunction "1_1") (pintype "passive"))
      (node (ref "X1") (pin "P$12") (pinfunction "S_P$12") (pintype "passive"))
    )
    (net (code "40") (name "Net-(X1F-S)") (class "Default")
      (node (ref "R19") (pin "1") (pinfunction "1_1") (pintype "passive"))
      (node (ref "X1") (pin "P$14") (pinfunction "S_P$14") (pintype "passive"))
    )
    (net (code "41") (name "POWER+") (class "Default")
      (node (ref "C10") (pin "1") (pinfunction "+_1") (pintype "passive"))
      (node (ref "C11") (pin "1") (pinfunction "+_1") (pintype "passive"))
      (node (ref "C22") (pin "1") (pinfunction "+_1") (pintype "passive"))
      (node (ref "C24") (pin "1") (pinfunction "+_1") (pintype "passive"))
      (node (ref "C5") (pin "1") (pinfunction "1_1") (pintype "passive"))
      (node (ref "DCDC12") (pin "1") (pinfunction "+VIN_1") (pintype "bidirectional"))
      (node (ref "DCDC24") (pin "1") (pinfunction "+VIN_1") (pintype "bidirectional"))
      (node (ref "DCDC5") (pin "1") (pinfunction "+VIN_1") (pintype "bidirectional"))
      (node (ref "J5") (pin "+") (pinfunction "VCC_+") (pintype "bidirectional"))
      (node (ref "R1") (pin "1") (pinfunction "1_1") (pintype "passive"))
      (node (ref "R11") (pin "2") (pinfunction "2_2") (pintype "passive"))
      (node (ref "R16") (pin "2") (pinfunction "2_2") (pintype "passive"))
      (node (ref "U10") (pin "1") (pinfunction "VCC_1") (pintype "power_in"))
    )
    (net (code "42") (name "POWER-") (class "Default")
      (node (ref "J5") (pin "-") (pinfunction "GND_-") (pintype "bidirectional"))
      (node (ref "R6") (pin "1") (pinfunction "1_1") (pintype "passive"))
      (node (ref "U5") (pin "2") (pinfunction "CSP_2") (pintype "bidirectional"))
    )
    (net (code "43") (name "POWER_12") (class "Default")
      (node (ref "DCDC12") (pin "4") (pinfunction "+VOUT_4") (pintype "bidirectional"))
      (node (ref "I12") (pin "1_2") (pinfunction "IP+_1_2") (pintype "input"))
    )
    (net (code "44") (name "POWER_24") (class "Default")
      (node (ref "DCDC24") (pin "3") (pinfunction "+VOUT_3") (pintype "bidirectional"))
      (node (ref "I24") (pin "1_2") (pinfunction "IP+_1_2") (pintype "input"))
    )
    (net (code "45") (name "SCL_BATT") (class "Default")
      (node (ref "U9") (pin "6") (pinfunction "SCL2_6") (pintype "bidirectional"))
      (node (ref "X1") (pin "P$8") (pinfunction "S_P$8") (pintype "passive"))
    )
    (net (code "46") (name "SCL_GAUGE") (class "Default")
      (node (ref "R9") (pin "2") (pinfunction "2_2") (pintype "passive"))
      (node (ref "U9") (pin "3") (pinfunction "SCL1_3") (pintype "bidirectional"))
    )
    (net (code "47") (name "SCL_TEMP") (class "Default")
      (node (ref "TMP_POWER") (pin "1") (pinfunction "SCL_1") (pintype "input"))
      (node (ref "X1") (pin "P$9") (pinfunction "S_P$9") (pintype "passive"))
    )
    (net (code "48") (name "SDA_BATT") (class "Default")
      (node (ref "U9") (pin "7") (pinfunction "SDA2_7") (pintype "bidirectional"))
      (node (ref "X1") (pin "P$10") (pinfunction "S_P$10") (pintype "passive"))
    )
    (net (code "49") (name "SDA_GAUGE") (class "Default")
      (node (ref "R10") (pin "2") (pinfunction "2_2") (pintype "passive"))
      (node (ref "U9") (pin "2") (pinfunction "SDA1_2") (pintype "bidirectional"))
    )
    (net (code "50") (name "SDA_TEMP") (class "Default")
      (node (ref "TMP_POWER") (pin "6") (pinfunction "SDA_6") (pintype "bidirectional"))
      (node (ref "X1") (pin "P$11") (pinfunction "S_P$11") (pintype "passive"))
    )
    (net (code "51") (name "VBATT_A") (class "Default")
      (node (ref "R1") (pin "2") (pinfunction "2_2") (pintype "passive"))
      (node (ref "R2") (pin "1") (pinfunction "1_1") (pintype "passive"))
      (node (ref "R4") (pin "2") (pinfunction "2_2") (pintype "passive"))
    )
    (net (code "52") (name "VBATT_B") (class "Default")
      (node (ref "R12") (pin "1") (pinfunction "1_1") (pintype "passive"))
      (node (ref "U11") (pin "1") (pinfunction "VOUT_1") (pintype "passive"))
      (node (ref "X1") (pin "P$6") (pinfunction "S_P$6") (pintype "passive"))
    )
    (net (code "53") (name "VCC_3.3") (class "Default")
      (node (ref "C6") (pin "1") (pinfunction "1_1") (pintype "passive"))
      (node (ref "C9") (pin "1") (pinfunction "1_1") (pintype "passive"))
      (node (ref "U6") (pin "6") (pinfunction "+VOUT_6") (pintype "bidirectional"))
      (node (ref "X1") (pin "P$4") (pinfunction "S_P$4") (pintype "passive"))
    )
    (net (code "54") (name "VCC_5") (class "Default")
      (node (ref "+5V") (pin "2") (pinfunction "2_2") (pintype "passive"))
      (node (ref "+5V") (pin "3") (pinfunction "3_3") (pintype "passive"))
      (node (ref "C12") (pin "1") (pinfunction "1_1") (pintype "passive"))
      (node (ref "C17") (pin "1") (pinfunction "1_1") (pintype "passive"))
      (node (ref "C18") (pin "1") (pinfunction "1_1") (pintype "passive"))
      (node (ref "C19") (pin "2") (pinfunction "2_2") (pintype "passive"))
      (node (ref "C20") (pin "1") (pinfunction "1_1") (pintype "passive"))
      (node (ref "C21") (pin "1") (pinfunction "1_1") (pintype "passive"))
      (node (ref "C23") (pin "1") (pinfunction "1_1") (pintype "passive"))
      (node (ref "C7") (pin "1") (pinfunction "1_1") (pintype "passive"))
      (node (ref "I12") (pin "12") (pinfunction "VCC_12") (pintype "power_in"))
      (node (ref "I24") (pin "12") (pinfunction "VCC_12") (pintype "power_in"))
      (node (ref "I5") (pin "12") (pinfunction "VCC_12") (pintype "power_in"))
      (node (ref "I5") (pin "3_4") (pinfunction "IP-_3_4") (pintype "input"))
      (node (ref "R13") (pin "2") (pinfunction "2_2") (pintype "passive"))
      (node (ref "TMP_POWER") (pin "3") (pinfunction "ADD1_3") (pintype "input"))
      (node (ref "TMP_POWER") (pin "4") (pinfunction "V+_4") (pintype "power_in"))
      (node (ref "U11") (pin "5") (pinfunction "VDD_5") (pintype "passive"))
      (node (ref "U20") (pin "1") (pinfunction "VCC1_1") (pintype "power_in"))
      (node (ref "U6") (pin "1") (pinfunction "+VIN_1") (pintype "bidirectional"))
      (node (ref "U9") (pin "8") (pinfunction "VCC2_8") (pintype "power_in"))
      (node (ref "X1") (pin "P$3") (pinfunction "S_P$3") (pintype "passive"))
    )
    (net (code "55") (name "VCC_12") (class "Default")
      (node (ref "+12V") (pin "2") (pinfunction "2_2") (pintype "passive"))
      (node (ref "+12V") (pin "3") (pinfunction "3_3") (pintype "passive"))
      (node (ref "C15") (pin "1") (pinfunction "+_1") (pintype "passive"))
      (node (ref "C16") (pin "1") (pinfunction "1_1") (pintype "passive"))
      (node (ref "I12") (pin "3_4") (pinfunction "IP-_3_4") (pintype "input"))
      (node (ref "INTEL/NUC") (pin "1") (pinfunction "1_1") (pintype "passive"))
      (node (ref "INTEL/NUC") (pin "3") (pinfunction "3_3") (pintype "passive"))
      (node (ref "J1") (pin "2") (pinfunction "A2_2") (pintype "passive"))
    )
    (net (code "56") (name "VCC_24") (class "Default")
      (node (ref "+24V") (pin "2") (pinfunction "2_2") (pintype "passive"))
      (node (ref "+24V") (pin "3") (pinfunction "3_3") (pintype "passive"))
      (node (ref "C13") (pin "1") (pinfunction "+_1") (pintype "passive"))
      (node (ref "C14") (pin "1") (pinfunction "1_1") (pintype "passive"))
      (node (ref "FAN_A") (pin "1") (pinfunction "1_1") (pintype "passive"))
      (node (ref "FAN_A") (pin "3") (pinfunction "3_3") (pintype "passive"))
      (node (ref "FAN_B") (pin "1") (pinfunction "1_1") (pintype "passive"))
      (node (ref "FAN_B") (pin "3") (pinfunction "3_3") (pintype "passive"))
      (node (ref "I24") (pin "3_4") (pinfunction "IP-_3_4") (pintype "input"))
      (node (ref "J2") (pin "2") (pinfunction "A2_2") (pintype "passive"))
      (node (ref "Q/M8") (pin "1") (pinfunction "1_1") (pintype "passive"))
      (node (ref "Q/M8") (pin "3") (pinfunction "3_3") (pintype "passive"))
    )
    (net (code "57") (name "unconnected-(DCDC5-REMOTE-Pad6)") (class "Default")
      (node (ref "DCDC5") (pin "6") (pinfunction "REMOTE_6") (pintype "bidirectional"))
    )
    (net (code "58") (name "unconnected-(I5-NC_6-Pad6)") (class "Default")
      (node (ref "I5") (pin "6") (pinfunction "NC_6_6") (pintype "passive"))
    )
    (net (code "59") (name "unconnected-(I5-NC_7-Pad7)") (class "Default")
      (node (ref "I5") (pin "7") (pinfunction "NC_7_7") (pintype "passive"))
    )
    (net (code "60") (name "unconnected-(I5-NC_8-Pad8)") (class "Default")
      (node (ref "I5") (pin "8") (pinfunction "NC_8_8") (pintype "passive"))
    )
    (net (code "61") (name "unconnected-(I5-NC_9-Pad9)") (class "Default")
      (node (ref "I5") (pin "9") (pinfunction "NC_9_9") (pintype "passive"))
    )
    (net (code "62") (name "unconnected-(I5-NC_11-Pad11)") (class "Default")
      (node (ref "I5") (pin "11") (pinfunction "NC_11_11") (pintype "passive"))
    )
    (net (code "63") (name "unconnected-(I12-NC_6-Pad6)") (class "Default")
      (node (ref "I12") (pin "6") (pinfunction "NC_6_6") (pintype "passive"))
    )
    (net (code "64") (name "unconnected-(I12-NC_7-Pad7)") (class "Default")
      (node (ref "I12") (pin "7") (pinfunction "NC_7_7") (pintype "passive"))
    )
    (net (code "65") (name "unconnected-(I12-NC_8-Pad8)") (class "Default")
      (node (ref "I12") (pin "8") (pinfunction "NC_8_8") (pintype "passive"))
    )
    (net (code "66") (name "unconnected-(I12-NC_9-Pad9)") (class "Default")
      (node (ref "I12") (pin "9") (pinfunction "NC_9_9") (pintype "passive"))
    )
    (net (code "67") (name "unconnected-(I12-NC_11-Pad11)") (class "Default")
      (node (ref "I12") (pin "11") (pinfunction "NC_11_11") (pintype "passive"))
    )
    (net (code "68") (name "unconnected-(I24-NC_6-Pad6)") (class "Default")
      (node (ref "I24") (pin "6") (pinfunction "NC_6_6") (pintype "passive"))
    )
    (net (code "69") (name "unconnected-(I24-NC_7-Pad7)") (class "Default")
      (node (ref "I24") (pin "7") (pinfunction "NC_7_7") (pintype "passive"))
    )
    (net (code "70") (name "unconnected-(I24-NC_8-Pad8)") (class "Default")
      (node (ref "I24") (pin "8") (pinfunction "NC_8_8") (pintype "passive"))
    )
    (net (code "71") (name "unconnected-(I24-NC_9-Pad9)") (class "Default")
      (node (ref "I24") (pin "9") (pinfunction "NC_9_9") (pintype "passive"))
    )
    (net (code "72") (name "unconnected-(I24-NC_11-Pad11)") (class "Default")
      (node (ref "I24") (pin "11") (pinfunction "NC_11_11") (pintype "passive"))
    )
    (net (code "73") (name "unconnected-(U3-NC-Pad8)") (class "Default")
      (node (ref "U3") (pin "8") (pinfunction "NC_8") (pintype "no_connect"))
    )
    (net (code "74") (name "unconnected-(U3-NC_2-Pad7)") (class "Default")
      (node (ref "U3") (pin "7") (pinfunction "NC_2_7") (pintype "no_connect"))
    )
    (net (code "75") (name "unconnected-(U5-ALRT1-Pad8)") (class "Default")
      (node (ref "U5") (pin "8") (pinfunction "ALRT1_8") (pintype "bidirectional"))
    )
    (net (code "76") (name "unconnected-(U5-THRM-Pad14)") (class "Default")
      (node (ref "U5") (pin "14") (pinfunction "THRM_14") (pintype "bidirectional"))
    )
    (net (code "77") (name "unconnected-(U6-NO_PIN-Pad5)") (class "Default")
      (node (ref "U6") (pin "5") (pinfunction "NO_PIN_5") (pintype "bidirectional"))
    )
    (net (code "78") (name "unconnected-(U20-IND-Pad11)") (class "Default")
      (node (ref "U20") (pin "11") (pinfunction "IND_11") (pintype "input"))
    )
    (net (code "79") (name "unconnected-(U20-OUTD-Pad6)") (class "Default")
      (node (ref "U20") (pin "6") (pinfunction "OUTD_6") (pintype "tri_state"))
    )
  )
)
